# MCU.net
KiCad netlist of a schematic drawn in Altium Designer
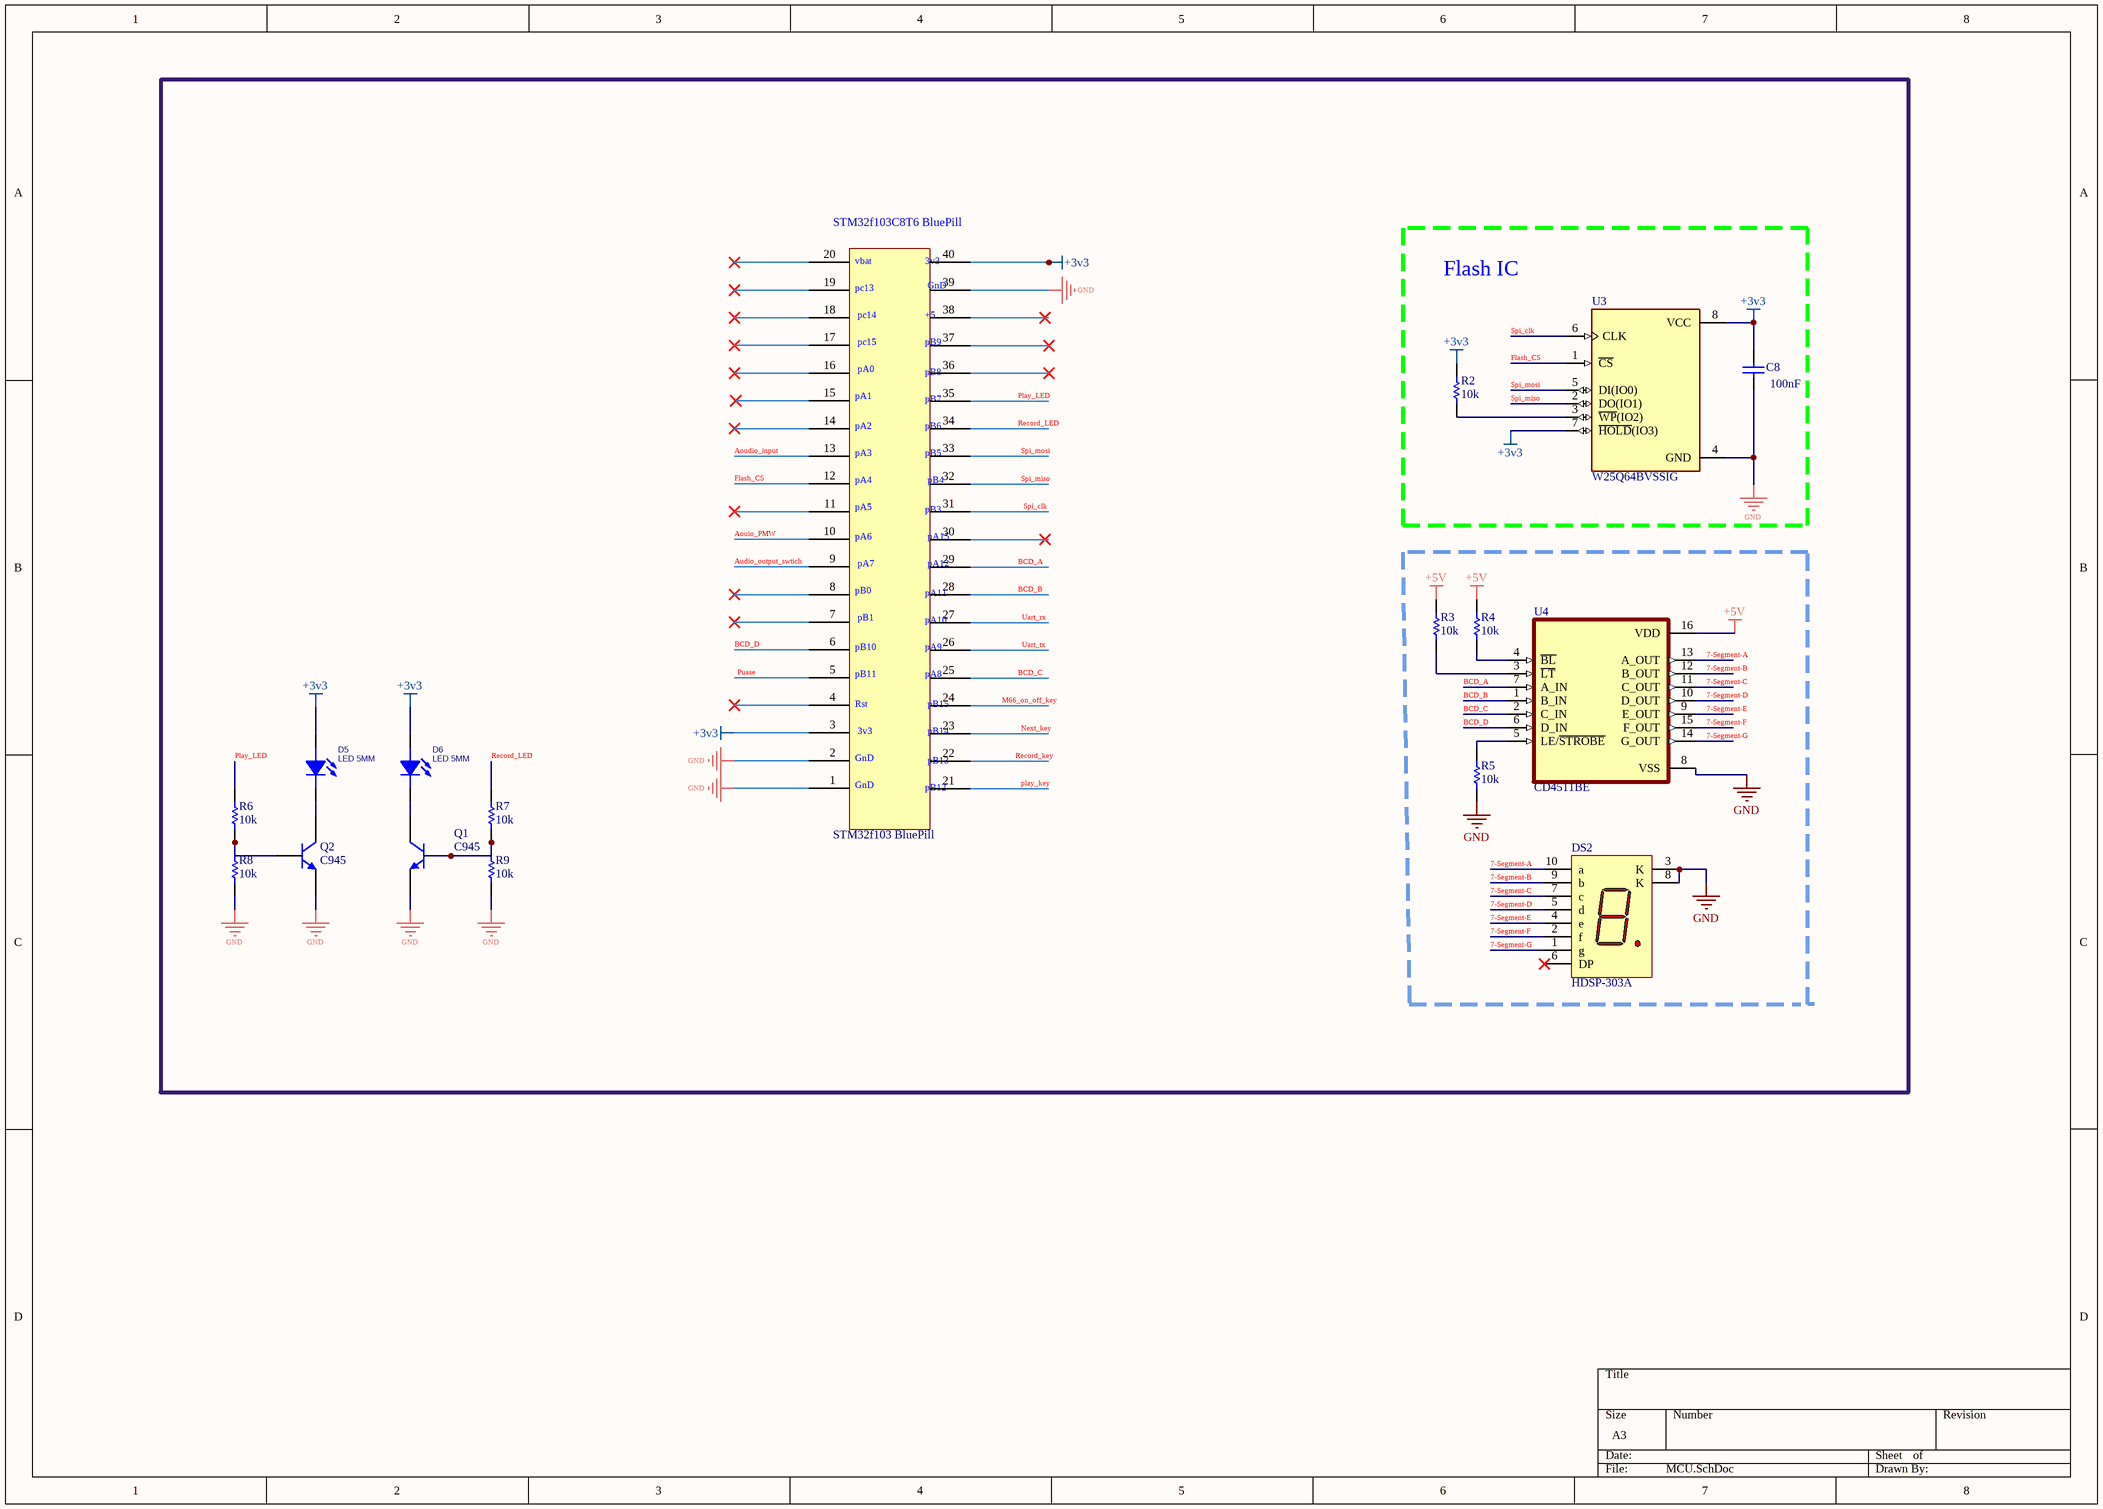
[diagram p0: MCU.SchDoc]

(export (version "E")
  (design (tool "Eeschema 10.0.6"))
  (components
    (comp (ref "C8")
      (value "100nF")
      (footprint "CAP805")
      (description "Capacitor")
      (fields (field (name "PUBLISHER") "Altium Limited"))
      (libsource (lib "componnect") (part "Cap"))
    )
    (comp (ref "D5")
      (value "LED 5MM")
      (footprint "LED5MM_GRN")
      (description "Light Emitting Diode")
      (fields (field (name "DESIGNER") "Abbas Basereh"))
      (libsource (lib "Schematic") (part "LED 5MM"))
    )
    (comp (ref "D6")
      (value "LED 5MM")
      (footprint "LED5MM_RED")
      (description "Light Emitting Diode")
      (fields (field (name "DESIGNER") "Abbas Basereh"))
      (libsource (lib "Schematic") (part "LED 5MM"))
    )
    (comp (ref "DS2")
      (value "HDSP-303A")
      (footprint "F-10")
      (description "10 mm Slim Font, AlGaAs 7-Segment Display: CC, RH DP")
      (fields (field (name "PUBLISHER") "Altium Limited"))
      (libsource (lib "Agilent LED Display 7-Segment, 1-Digit") (part "HDSP-303A"))
    )
    (comp (ref "Q1")
      (value "C945")
      (footprint "C945")
      (description "NPN Transistor")
      (fields (field (name "DESIGNER") "Saeid Jorablo"))
      (libsource (lib "Schematic") (part "C945 2"))
    )
    (comp (ref "Q2")
      (value "C945")
      (footprint "C945")
      (description "NPN Transistor")
      (fields (field (name "DESIGNER") "Saeid Jorablo"))
      (libsource (lib "Schematic") (part "C945 2"))
    )
    (comp (ref "R2")
      (value "10k")
      (footprint "RES0805")
      (description "RES 0805")
      (fields (field (name "DESIGNER") "Abbas Basereh"))
      (libsource (lib "componnect") (part "RES 0805 0.125W_1"))
    )
    (comp (ref "R3")
      (value "10k")
      (footprint "RES0805")
      (description "RES 0805")
      (fields (field (name "DESIGNER") "Abbas Basereh"))
      (libsource (lib "componnect") (part "RES 0805 0.125W_1"))
    )
    (comp (ref "R4")
      (value "10k")
      (footprint "RES0805")
      (description "RES 0805")
      (fields (field (name "DESIGNER") "Abbas Basereh"))
      (libsource (lib "componnect") (part "RES 0805 0.125W_1"))
    )
    (comp (ref "R5")
      (value "10k")
      (footprint "RES0805")
      (description "RES 0805")
      (fields (field (name "DESIGNER") "Abbas Basereh"))
      (libsource (lib "componnect") (part "RES 0805 0.125W_1"))
    )
    (comp (ref "R6")
      (value "10k")
      (footprint "RES0805")
      (description "RES 0805")
      (fields (field (name "DESIGNER") "Abbas Basereh"))
      (libsource (lib "componnect") (part "RES 0805 0.125W_1"))
    )
    (comp (ref "R7")
      (value "10k")
      (footprint "RES0805")
      (description "RES 0805")
      (fields (field (name "DESIGNER") "Abbas Basereh"))
      (libsource (lib "componnect") (part "RES 0805 0.125W_1"))
    )
    (comp (ref "R8")
      (value "10k")
      (footprint "RES0805")
      (description "RES 0805")
      (fields (field (name "DESIGNER") "Abbas Basereh"))
      (libsource (lib "componnect") (part "RES 0805 0.125W_1"))
    )
    (comp (ref "R9")
      (value "10k")
      (footprint "RES0805")
      (description "RES 0805")
      (fields (field (name "DESIGNER") "Abbas Basereh"))
      (libsource (lib "componnect") (part "RES 0805 0.125W_1"))
    )
    (comp (ref "STM1")
      (value "STM32f103 BluePill")
      (footprint "BluePill")
      (libsource (lib "BluePill") (part "STM32f103 BluePill"))
    )
    (comp (ref "U3")
      (value "W25Q64BVSSIG")
      (footprint "W25Q64BVSSIG:SOIC127P790X216-8N")
      (description "IC FLASH 64MBIT 80MHZ 8SOIC")
      (fields (field (name "MF") "{'manufacturer': u'Winbond Electronics'}"))
      (libsource (lib "*") (part "W25Q64BVSSIG"))
    )
    (comp (ref "U4")
      (value "CD4511BE")
      (footprint "DIP794W45P254L1969H508Q16")
      (libsource (lib "CD4511BE") (part "CD4511BE"))
    )
  )
  (nets
    (net (code "1") (name "+3v3") (class "Default")
      (node (ref "C8") (pin "2") (pinfunction "2_2") (pintype "passive"))
      (node (ref "D5") (pin "1") (pinfunction "ANODE_1") (pintype "passive"))
      (node (ref "D6") (pin "1") (pinfunction "ANODE_1") (pintype "passive"))
      (node (ref "R2") (pin "2") (pinfunction "2_2") (pintype "passive"))
      (node (ref "STM1") (pin "3") (pinfunction "3_3") (pintype "passive"))
      (node (ref "STM1") (pin "40") (pinfunction "40_40") (pintype "passive"))
      (node (ref "U3") (pin "7") (pinfunction "~{HOLD}(IO3)_7") (pintype "bidirectional"))
      (node (ref "U3") (pin "8") (pinfunction "VCC_8") (pintype "power_in"))
    )
    (net (code "2") (name "+5V") (class "Default")
      (node (ref "R3") (pin "1") (pinfunction "1_1") (pintype "passive"))
      (node (ref "R4") (pin "1") (pinfunction "1_1") (pintype "passive"))
      (node (ref "U4") (pin "16") (pinfunction "VDD_16") (pintype "power_in"))
    )
    (net (code "3") (name "/7-Segment-A") (class "Default")
      (node (ref "DS2") (pin "10") (pinfunction "a_10") (pintype "passive"))
      (node (ref "U4") (pin "13") (pinfunction "A_OUT_13") (pintype "output"))
    )
    (net (code "4") (name "/7-Segment-B") (class "Default")
      (node (ref "DS2") (pin "9") (pinfunction "b_9") (pintype "passive"))
      (node (ref "U4") (pin "12") (pinfunction "B_OUT_12") (pintype "output"))
    )
    (net (code "5") (name "/7-Segment-C") (class "Default")
      (node (ref "DS2") (pin "7") (pinfunction "c_7") (pintype "passive"))
      (node (ref "U4") (pin "11") (pinfunction "C_OUT_11") (pintype "output"))
    )
    (net (code "6") (name "/7-Segment-D") (class "Default")
      (node (ref "DS2") (pin "5") (pinfunction "d_5") (pintype "passive"))
      (node (ref "U4") (pin "10") (pinfunction "D_OUT_10") (pintype "output"))
    )
    (net (code "7") (name "/7-Segment-E") (class "Default")
      (node (ref "DS2") (pin "4") (pinfunction "e_4") (pintype "passive"))
      (node (ref "U4") (pin "9") (pinfunction "E_OUT_9") (pintype "output"))
    )
    (net (code "8") (name "/7-Segment-F") (class "Default")
      (node (ref "DS2") (pin "2") (pinfunction "f_2") (pintype "passive"))
      (node (ref "U4") (pin "15") (pinfunction "F_OUT_15") (pintype "output"))
    )
    (net (code "9") (name "/7-Segment-G") (class "Default")
      (node (ref "DS2") (pin "1") (pinfunction "g_1") (pintype "passive"))
      (node (ref "U4") (pin "14") (pinfunction "G_OUT_14") (pintype "output"))
    )
    (net (code "10") (name "/Aoudio_input") (class "Default")
      (node (ref "STM1") (pin "13") (pinfunction "13_13") (pintype "passive"))
    )
    (net (code "11") (name "/Aouio_PMW") (class "Default")
      (node (ref "STM1") (pin "10") (pinfunction "10_10") (pintype "passive"))
    )
    (net (code "12") (name "/Audio_output_swtich") (class "Default")
      (node (ref "STM1") (pin "9") (pinfunction "9_9") (pintype "passive"))
    )
    (net (code "13") (name "/BCD_A") (class "Default")
      (node (ref "STM1") (pin "29") (pinfunction "29_29") (pintype "passive"))
      (node (ref "U4") (pin "7") (pinfunction "A_IN_7") (pintype "input"))
    )
    (net (code "14") (name "/BCD_B") (class "Default")
      (node (ref "STM1") (pin "28") (pinfunction "28_28") (pintype "passive"))
      (node (ref "U4") (pin "1") (pinfunction "B_IN_1") (pintype "input"))
    )
    (net (code "15") (name "/BCD_C") (class "Default")
      (node (ref "STM1") (pin "25") (pinfunction "25_25") (pintype "passive"))
      (node (ref "U4") (pin "2") (pinfunction "C_IN_2") (pintype "input"))
    )
    (net (code "16") (name "/BCD_D") (class "Default")
      (node (ref "STM1") (pin "6") (pinfunction "6_6") (pintype "passive"))
      (node (ref "U4") (pin "6") (pinfunction "D_IN_6") (pintype "input"))
    )
    (net (code "17") (name "/Flash_CS") (class "Default")
      (node (ref "STM1") (pin "12") (pinfunction "12_12") (pintype "passive"))
      (node (ref "U3") (pin "1") (pinfunction "~{CS}_1") (pintype "input"))
    )
    (net (code "18") (name "/M66_on_off_key") (class "Default")
      (node (ref "STM1") (pin "24") (pinfunction "24_24") (pintype "passive"))
    )
    (net (code "19") (name "/Next_key") (class "Default")
      (node (ref "STM1") (pin "23") (pinfunction "23_23") (pintype "passive"))
    )
    (net (code "20") (name "/Play_LED") (class "Default")
      (node (ref "R6") (pin "2") (pinfunction "2_2") (pintype "passive"))
      (node (ref "STM1") (pin "35") (pinfunction "35_35") (pintype "passive"))
    )
    (net (code "21") (name "/Puase") (class "Default")
      (node (ref "STM1") (pin "5") (pinfunction "5_5") (pintype "passive"))
    )
    (net (code "22") (name "/Record_LED") (class "Default")
      (node (ref "R7") (pin "2") (pinfunction "2_2") (pintype "passive"))
      (node (ref "STM1") (pin "34") (pinfunction "34_34") (pintype "passive"))
    )
    (net (code "23") (name "/Record_key") (class "Default")
      (node (ref "STM1") (pin "22") (pinfunction "22_22") (pintype "passive"))
    )
    (net (code "24") (name "/Spi_clk") (class "Default")
      (node (ref "STM1") (pin "31") (pinfunction "31_31") (pintype "passive"))
      (node (ref "U3") (pin "6") (pinfunction "CLK_6") (pintype "input"))
    )
    (net (code "25") (name "/Spi_miso") (class "Default")
      (node (ref "STM1") (pin "32") (pinfunction "32_32") (pintype "passive"))
      (node (ref "U3") (pin "2") (pinfunction "DO(IO1)_2") (pintype "bidirectional"))
    )
    (net (code "26") (name "/Spi_mosi") (class "Default")
      (node (ref "STM1") (pin "33") (pinfunction "33_33") (pintype "passive"))
      (node (ref "U3") (pin "5") (pinfunction "DI(IO0)_5") (pintype "bidirectional"))
    )
    (net (code "27") (name "/Uart_rx") (class "Default")
      (node (ref "STM1") (pin "27") (pinfunction "27_27") (pintype "passive"))
    )
    (net (code "28") (name "/Uart_tx") (class "Default")
      (node (ref "STM1") (pin "26") (pinfunction "26_26") (pintype "passive"))
    )
    (net (code "29") (name "/play_key") (class "Default")
      (node (ref "STM1") (pin "21") (pinfunction "21_21") (pintype "passive"))
    )
    (net (code "30") (name "GND") (class "Default")
      (node (ref "C8") (pin "1") (pinfunction "1_1") (pintype "passive"))
      (node (ref "DS2") (pin "3") (pinfunction "K_3") (pintype "passive"))
      (node (ref "DS2") (pin "8") (pinfunction "K_8") (pintype "passive"))
      (node (ref "Q1") (pin "1") (pinfunction "E_1") (pintype "passive"))
      (node (ref "Q2") (pin "1") (pinfunction "E_1") (pintype "passive"))
      (node (ref "R5") (pin "1") (pinfunction "1_1") (pintype "passive"))
      (node (ref "R8") (pin "1") (pinfunction "1_1") (pintype "passive"))
      (node (ref "R9") (pin "1") (pinfunction "1_1") (pintype "passive"))
      (node (ref "STM1") (pin "1") (pinfunction "1_1") (pintype "passive"))
      (node (ref "STM1") (pin "2") (pinfunction "2_2") (pintype "passive"))
      (node (ref "STM1") (pin "39") (pinfunction "39_39") (pintype "passive"))
      (node (ref "U3") (pin "4") (pinfunction "GND_4") (pintype "power_in"))
      (node (ref "U4") (pin "8") (pinfunction "VSS_8") (pintype "power_in"))
    )
    (net (code "31") (name "Net-(D5-CATHODE)") (class "Default")
      (node (ref "D5") (pin "2") (pinfunction "CATHODE_2") (pintype "passive"))
      (node (ref "Q2") (pin "2") (pinfunction "C_2") (pintype "passive"))
    )
    (net (code "32") (name "Net-(D6-CATHODE)") (class "Default")
      (node (ref "D6") (pin "2") (pinfunction "CATHODE_2") (pintype "passive"))
      (node (ref "Q1") (pin "2") (pinfunction "C_2") (pintype "passive"))
    )
    (net (code "33") (name "Net-(Q1-B)") (class "Default")
      (node (ref "Q1") (pin "3") (pinfunction "B_3") (pintype "passive"))
      (node (ref "R7") (pin "1") (pinfunction "1_1") (pintype "passive"))
      (node (ref "R9") (pin "2") (pinfunction "2_2") (pintype "passive"))
    )
    (net (code "34") (name "Net-(Q2-B)") (class "Default")
      (node (ref "Q2") (pin "3") (pinfunction "B_3") (pintype "passive"))
      (node (ref "R6") (pin "1") (pinfunction "1_1") (pintype "passive"))
      (node (ref "R8") (pin "2") (pinfunction "2_2") (pintype "passive"))
    )
    (net (code "35") (name "Net-(U3-~{WP}(IO2))") (class "Default")
      (node (ref "R2") (pin "1") (pinfunction "1_1") (pintype "passive"))
      (node (ref "U3") (pin "3") (pinfunction "~{WP}(IO2)_3") (pintype "bidirectional"))
    )
    (net (code "36") (name "Net-(U4-LE{slash}~{STROBE})") (class "Default")
      (node (ref "R5") (pin "2") (pinfunction "2_2") (pintype "passive"))
      (node (ref "U4") (pin "5") (pinfunction "LE/~{STROBE}_5") (pintype "input"))
    )
    (net (code "37") (name "Net-(U4-~{BL})") (class "Default")
      (node (ref "R4") (pin "2") (pinfunction "2_2") (pintype "passive"))
      (node (ref "U4") (pin "4") (pinfunction "~{BL}_4") (pintype "input"))
    )
    (net (code "38") (name "Net-(U4-~{LT})") (class "Default")
      (node (ref "R3") (pin "2") (pinfunction "2_2") (pintype "passive"))
      (node (ref "U4") (pin "3") (pinfunction "~{LT}_3") (pintype "input"))
    )
    (net (code "39") (name "unconnected-(DS2-DP-Pad6)") (class "Default")
      (node (ref "DS2") (pin "6") (pinfunction "DP_6") (pintype "passive+no_connect"))
    )
    (net (code "40") (name "unconnected-(STM1-Pad4)") (class "Default")
      (node (ref "STM1") (pin "4") (pinfunction "4_4") (pintype "passive+no_connect"))
    )
    (net (code "41") (name "unconnected-(STM1-Pad7)") (class "Default")
      (node (ref "STM1") (pin "7") (pinfunction "7_7") (pintype "passive"))
    )
    (net (code "42") (name "unconnected-(STM1-Pad8)") (class "Default")
      (node (ref "STM1") (pin "8") (pinfunction "8_8") (pintype "passive+no_connect"))
    )
    (net (code "43") (name "unconnected-(STM1-Pad11)") (class "Default")
      (node (ref "STM1") (pin "11") (pinfunction "11_11") (pintype "passive+no_connect"))
    )
    (net (code "44") (name "unconnected-(STM1-Pad14)") (class "Default")
      (node (ref "STM1") (pin "14") (pinfunction "14_14") (pintype "passive+no_connect"))
    )
    (net (code "45") (name "unconnected-(STM1-Pad15)") (class "Default")
      (node (ref "STM1") (pin "15") (pinfunction "15_15") (pintype "passive+no_connect"))
    )
    (net (code "46") (name "unconnected-(STM1-Pad16)") (class "Default")
      (node (ref "STM1") (pin "16") (pinfunction "16_16") (pintype "passive+no_connect"))
    )
    (net (code "47") (name "unconnected-(STM1-Pad17)") (class "Default")
      (node (ref "STM1") (pin "17") (pinfunction "17_17") (pintype "passive+no_connect"))
    )
    (net (code "48") (name "unconnected-(STM1-Pad18)") (class "Default")
      (node (ref "STM1") (pin "18") (pinfunction "18_18") (pintype "passive+no_connect"))
    )
    (net (code "49") (name "unconnected-(STM1-Pad19)") (class "Default")
      (node (ref "STM1") (pin "19") (pinfunction "19_19") (pintype "passive+no_connect"))
    )
    (net (code "50") (name "unconnected-(STM1-Pad20)") (class "Default")
      (node (ref "STM1") (pin "20") (pinfunction "20_20") (pintype "passive+no_connect"))
    )
    (net (code "51") (name "unconnected-(STM1-Pad30)") (class "Default")
      (node (ref "STM1") (pin "30") (pinfunction "30_30") (pintype "passive"))
    )
    (net (code "52") (name "unconnected-(STM1-Pad36)") (class "Default")
      (node (ref "STM1") (pin "36") (pinfunction "36_36") (pintype "passive+no_connect"))
    )
    (net (code "53") (name "unconnected-(STM1-Pad37)") (class "Default")
      (node (ref "STM1") (pin "37") (pinfunction "37_37") (pintype "passive+no_connect"))
    )
    (net (code "54") (name "unconnected-(STM1-Pad38)") (class "Default")
      (node (ref "STM1") (pin "38") (pinfunction "38_38") (pintype "passive"))
    )
  )
)
